# Array.net
KiCad netlist of a schematic drawn in Altium Designer
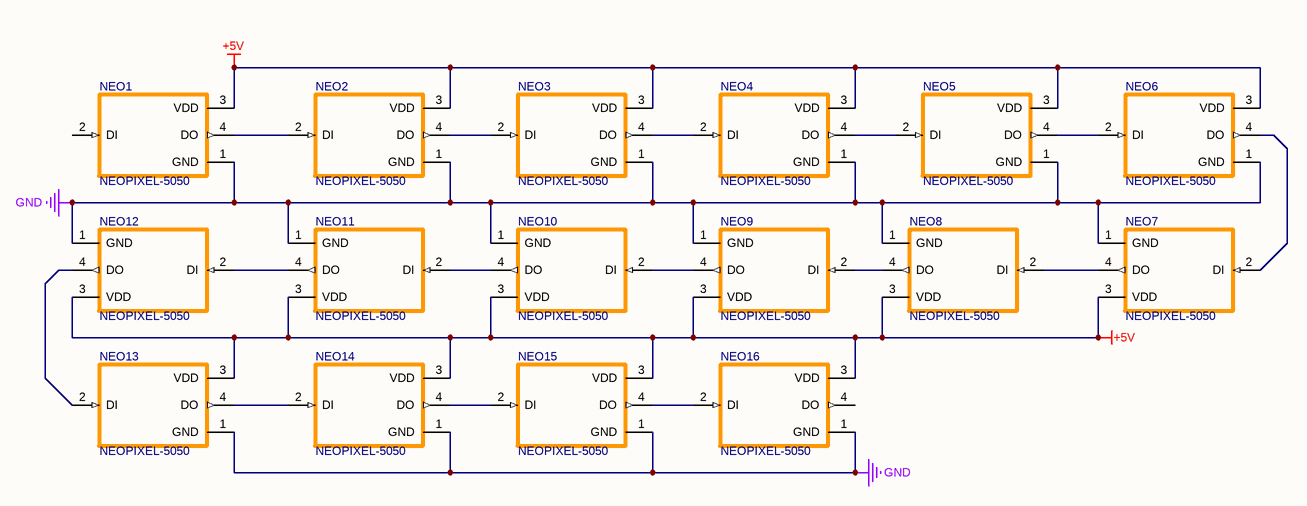
[diagram p0: Array.SchDoc]

(export (version "E")
  (design (tool "Eeschema 10.0.6"))
  (components
    (comp (ref "NEO1")
      (value "NEOPIXEL-5050")
      (footprint "NEOPIXEL-5050")
      (libsource (lib "RC") (part "NEOPIXEL-5050"))
    )
    (comp (ref "NEO2")
      (value "NEOPIXEL-5050")
      (footprint "NEOPIXEL-5050")
      (libsource (lib "RC") (part "NEOPIXEL-5050"))
    )
    (comp (ref "NEO3")
      (value "NEOPIXEL-5050")
      (footprint "NEOPIXEL-5050")
      (libsource (lib "RC") (part "NEOPIXEL-5050"))
    )
    (comp (ref "NEO4")
      (value "NEOPIXEL-5050")
      (footprint "NEOPIXEL-5050")
      (libsource (lib "RC") (part "NEOPIXEL-5050"))
    )
    (comp (ref "NEO5")
      (value "NEOPIXEL-5050")
      (footprint "NEOPIXEL-5050")
      (libsource (lib "RC") (part "NEOPIXEL-5050"))
    )
    (comp (ref "NEO6")
      (value "NEOPIXEL-5050")
      (footprint "NEOPIXEL-5050")
      (libsource (lib "RC") (part "NEOPIXEL-5050"))
    )
    (comp (ref "NEO7")
      (value "NEOPIXEL-5050")
      (footprint "NEOPIXEL-5050")
      (libsource (lib "") (part "NEOPIXEL-5050_1"))
    )
    (comp (ref "NEO8")
      (value "NEOPIXEL-5050")
      (footprint "NEOPIXEL-5050")
      (libsource (lib "") (part "NEOPIXEL-5050_1"))
    )
    (comp (ref "NEO9")
      (value "NEOPIXEL-5050")
      (footprint "NEOPIXEL-5050")
      (libsource (lib "") (part "NEOPIXEL-5050_1"))
    )
    (comp (ref "NEO10")
      (value "NEOPIXEL-5050")
      (footprint "NEOPIXEL-5050")
      (libsource (lib "") (part "NEOPIXEL-5050_1"))
    )
    (comp (ref "NEO11")
      (value "NEOPIXEL-5050")
      (footprint "NEOPIXEL-5050")
      (libsource (lib "") (part "NEOPIXEL-5050_1"))
    )
    (comp (ref "NEO12")
      (value "NEOPIXEL-5050")
      (footprint "NEOPIXEL-5050")
      (libsource (lib "") (part "NEOPIXEL-5050_1"))
    )
    (comp (ref "NEO13")
      (value "NEOPIXEL-5050")
      (footprint "NEOPIXEL-5050")
      (libsource (lib "RC") (part "NEOPIXEL-5050"))
    )
    (comp (ref "NEO14")
      (value "NEOPIXEL-5050")
      (footprint "NEOPIXEL-5050")
      (libsource (lib "RC") (part "NEOPIXEL-5050"))
    )
    (comp (ref "NEO15")
      (value "NEOPIXEL-5050")
      (footprint "NEOPIXEL-5050")
      (libsource (lib "RC") (part "NEOPIXEL-5050"))
    )
    (comp (ref "NEO16")
      (value "NEOPIXEL-5050")
      (footprint "NEOPIXEL-5050")
      (libsource (lib "RC") (part "NEOPIXEL-5050"))
    )
  )
  (nets
    (net (code "1") (name "+5V") (class "Default")
      (node (ref "NEO1") (pin "3") (pinfunction "VDD_3") (pintype "power_in"))
      (node (ref "NEO10") (pin "3") (pinfunction "VDD_3") (pintype "power_in"))
      (node (ref "NEO11") (pin "3") (pinfunction "VDD_3") (pintype "power_in"))
      (node (ref "NEO12") (pin "3") (pinfunction "VDD_3") (pintype "power_in"))
      (node (ref "NEO13") (pin "3") (pinfunction "VDD_3") (pintype "power_in"))
      (node (ref "NEO14") (pin "3") (pinfunction "VDD_3") (pintype "power_in"))
      (node (ref "NEO15") (pin "3") (pinfunction "VDD_3") (pintype "power_in"))
      (node (ref "NEO16") (pin "3") (pinfunction "VDD_3") (pintype "power_in"))
      (node (ref "NEO2") (pin "3") (pinfunction "VDD_3") (pintype "power_in"))
      (node (ref "NEO3") (pin "3") (pinfunction "VDD_3") (pintype "power_in"))
      (node (ref "NEO4") (pin "3") (pinfunction "VDD_3") (pintype "power_in"))
      (node (ref "NEO5") (pin "3") (pinfunction "VDD_3") (pintype "power_in"))
      (node (ref "NEO6") (pin "3") (pinfunction "VDD_3") (pintype "power_in"))
      (node (ref "NEO7") (pin "3") (pinfunction "VDD_3") (pintype "power_in"))
      (node (ref "NEO8") (pin "3") (pinfunction "VDD_3") (pintype "power_in"))
      (node (ref "NEO9") (pin "3") (pinfunction "VDD_3") (pintype "power_in"))
    )
    (net (code "2") (name "GND") (class "Default")
      (node (ref "NEO1") (pin "1") (pinfunction "GND_1") (pintype "power_in"))
      (node (ref "NEO10") (pin "1") (pinfunction "GND_1") (pintype "power_in"))
      (node (ref "NEO11") (pin "1") (pinfunction "GND_1") (pintype "power_in"))
      (node (ref "NEO12") (pin "1") (pinfunction "GND_1") (pintype "power_in"))
      (node (ref "NEO13") (pin "1") (pinfunction "GND_1") (pintype "power_in"))
      (node (ref "NEO14") (pin "1") (pinfunction "GND_1") (pintype "power_in"))
      (node (ref "NEO15") (pin "1") (pinfunction "GND_1") (pintype "power_in"))
      (node (ref "NEO16") (pin "1") (pinfunction "GND_1") (pintype "power_in"))
      (node (ref "NEO2") (pin "1") (pinfunction "GND_1") (pintype "power_in"))
      (node (ref "NEO3") (pin "1") (pinfunction "GND_1") (pintype "power_in"))
      (node (ref "NEO4") (pin "1") (pinfunction "GND_1") (pintype "power_in"))
      (node (ref "NEO5") (pin "1") (pinfunction "GND_1") (pintype "power_in"))
      (node (ref "NEO6") (pin "1") (pinfunction "GND_1") (pintype "power_in"))
      (node (ref "NEO7") (pin "1") (pinfunction "GND_1") (pintype "power_in"))
      (node (ref "NEO8") (pin "1") (pinfunction "GND_1") (pintype "power_in"))
      (node (ref "NEO9") (pin "1") (pinfunction "GND_1") (pintype "power_in"))
    )
    (net (code "3") (name "Net-(NEO1-DO)") (class "Default")
      (node (ref "NEO1") (pin "4") (pinfunction "DO_4") (pintype "output"))
      (node (ref "NEO2") (pin "2") (pinfunction "DI_2") (pintype "input"))
    )
    (net (code "4") (name "Net-(NEO2-DO)") (class "Default")
      (node (ref "NEO2") (pin "4") (pinfunction "DO_4") (pintype "output"))
      (node (ref "NEO3") (pin "2") (pinfunction "DI_2") (pintype "input"))
    )
    (net (code "5") (name "Net-(NEO3-DO)") (class "Default")
      (node (ref "NEO3") (pin "4") (pinfunction "DO_4") (pintype "output"))
      (node (ref "NEO4") (pin "2") (pinfunction "DI_2") (pintype "input"))
    )
    (net (code "6") (name "Net-(NEO4-DO)") (class "Default")
      (node (ref "NEO4") (pin "4") (pinfunction "DO_4") (pintype "output"))
      (node (ref "NEO5") (pin "2") (pinfunction "DI_2") (pintype "input"))
    )
    (net (code "7") (name "Net-(NEO5-DO)") (class "Default")
      (node (ref "NEO5") (pin "4") (pinfunction "DO_4") (pintype "output"))
      (node (ref "NEO6") (pin "2") (pinfunction "DI_2") (pintype "input"))
    )
    (net (code "8") (name "Net-(NEO6-DO)") (class "Default")
      (node (ref "NEO6") (pin "4") (pinfunction "DO_4") (pintype "output"))
      (node (ref "NEO7") (pin "2") (pinfunction "DI_2") (pintype "input"))
    )
    (net (code "9") (name "Net-(NEO7-DO)") (class "Default")
      (node (ref "NEO7") (pin "4") (pinfunction "DO_4") (pintype "output"))
      (node (ref "NEO8") (pin "2") (pinfunction "DI_2") (pintype "input"))
    )
    (net (code "10") (name "Net-(NEO8-DO)") (class "Default")
      (node (ref "NEO8") (pin "4") (pinfunction "DO_4") (pintype "output"))
      (node (ref "NEO9") (pin "2") (pinfunction "DI_2") (pintype "input"))
    )
    (net (code "11") (name "Net-(NEO10-DI)") (class "Default")
      (node (ref "NEO10") (pin "2") (pinfunction "DI_2") (pintype "input"))
      (node (ref "NEO9") (pin "4") (pinfunction "DO_4") (pintype "output"))
    )
    (net (code "12") (name "Net-(NEO10-DO)") (class "Default")
      (node (ref "NEO10") (pin "4") (pinfunction "DO_4") (pintype "output"))
      (node (ref "NEO11") (pin "2") (pinfunction "DI_2") (pintype "input"))
    )
    (net (code "13") (name "Net-(NEO11-DO)") (class "Default")
      (node (ref "NEO11") (pin "4") (pinfunction "DO_4") (pintype "output"))
      (node (ref "NEO12") (pin "2") (pinfunction "DI_2") (pintype "input"))
    )
    (net (code "14") (name "Net-(NEO12-DO)") (class "Default")
      (node (ref "NEO12") (pin "4") (pinfunction "DO_4") (pintype "output"))
      (node (ref "NEO13") (pin "2") (pinfunction "DI_2") (pintype "input"))
    )
    (net (code "15") (name "Net-(NEO13-DO)") (class "Default")
      (node (ref "NEO13") (pin "4") (pinfunction "DO_4") (pintype "output"))
      (node (ref "NEO14") (pin "2") (pinfunction "DI_2") (pintype "input"))
    )
    (net (code "16") (name "Net-(NEO14-DO)") (class "Default")
      (node (ref "NEO14") (pin "4") (pinfunction "DO_4") (pintype "output"))
      (node (ref "NEO15") (pin "2") (pinfunction "DI_2") (pintype "input"))
    )
    (net (code "17") (name "Net-(NEO15-DO)") (class "Default")
      (node (ref "NEO15") (pin "4") (pinfunction "DO_4") (pintype "output"))
      (node (ref "NEO16") (pin "2") (pinfunction "DI_2") (pintype "input"))
    )
    (net (code "18") (name "unconnected-(NEO1-DI-Pad2)") (class "Default")
      (node (ref "NEO1") (pin "2") (pinfunction "DI_2") (pintype "input"))
    )
    (net (code "19") (name "unconnected-(NEO16-DO-Pad4)") (class "Default")
      (node (ref "NEO16") (pin "4") (pinfunction "DO_4") (pintype "output"))
    )
  )
)
